# McPiFace-60mmFan-V3_1.net
KiCad netlist of a schematic drawn in EAGLE
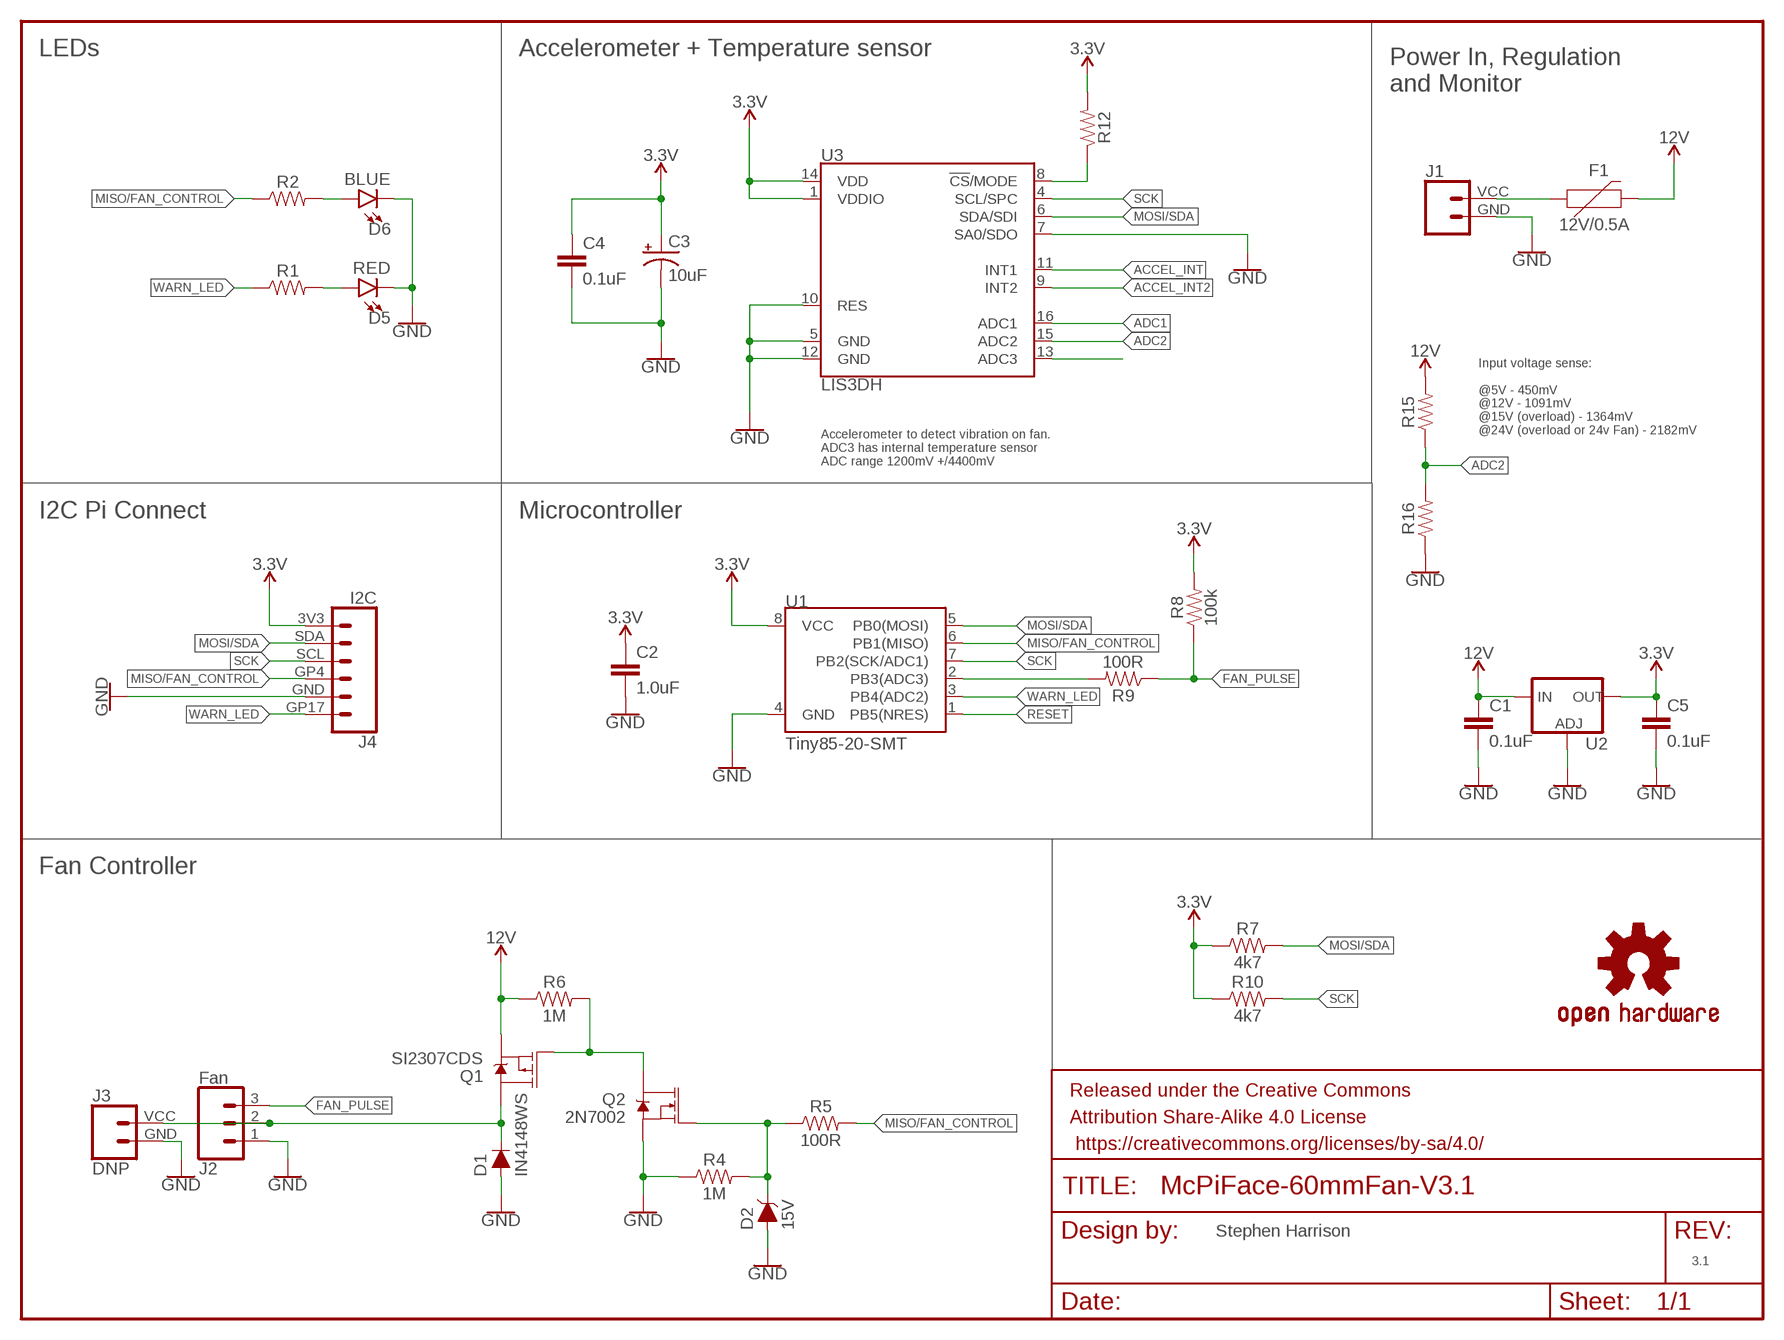
[diagram p0: schematic, sheet 1]

(export (version "E")
  (design (tool "Eeschema 10.0.6"))
  (components
    (comp (ref "C1")
      (value "0.1uF")
      (footprint "eagle-import:0805")
      (libsource (lib "eagle-import") (part "0.1UF-0805-25V"))
    )
    (comp (ref "C2")
      (value "1.0uF")
      (footprint "eagle-import:0805")
      (libsource (lib "eagle-import") (part "1.0UF-0805-25V-10%"))
    )
    (comp (ref "C3")
      (value "10uF")
      (footprint "eagle-import:EIA3216")
      (libsource (lib "eagle-import") (part "10UF-16V-10%(TANT)"))
    )
    (comp (ref "C4")
      (value "0.1uF")
      (footprint "eagle-import:0805")
      (libsource (lib "eagle-import") (part "1.0UF-0805-25V-10%"))
    )
    (comp (ref "C5")
      (value "0.1uF")
      (footprint "eagle-import:0805")
      (libsource (lib "eagle-import") (part "0.1UF-0805-25V"))
    )
    (comp (ref "D1")
      (value "IN4148WS")
      (footprint "eagle-import:SOD-323")
      (libsource (lib "eagle-import") (part "DIODE-BAS16J"))
    )
    (comp (ref "D2")
      (value "15V")
      (footprint "eagle-import:SOD-323")
      (libsource (lib "eagle-import") (part "DIODE-ZENER-BZT52C3V6S"))
    )
    (comp (ref "D5")
      (value "RED")
      (footprint "eagle-import:LED-1206")
      (libsource (lib "eagle-import") (part "LED1206"))
    )
    (comp (ref "D6")
      (value "BLUE")
      (footprint "eagle-import:LED-1206")
      (libsource (lib "eagle-import") (part "LED1206"))
    )
    (comp (ref "F1")
      (value "12V/0.5A")
      (footprint "eagle-import:1206")
      (libsource (lib "eagle-import") (part "PPTC_HALF-AMP"))
    )
    (comp (ref "FRAME1")
      (value "FRAME-LETTER")
      (footprint "eagle-import:CREATIVE_COMMONS")
      (libsource (lib "eagle-import") (part "FRAME-LETTER"))
    )
    (comp (ref "J1")
      (value "CONN_024UCON-15767")
      (footprint "eagle-import:JST-2-SMD-VERT")
      (libsource (lib "eagle-import") (part "CONN_024UCON-15767"))
    )
    (comp (ref "J2")
      (value "Fan")
      (footprint "eagle-import:JST-3-SMD")
      (fields (field (name "MFG") "S3B-PH-SM4-TB(LF)(SN)"))
      (libsource (lib "eagle-import") (part "CONN_03JST-SMD"))
    )
    (comp (ref "J3")
      (value "DNP")
      (footprint "eagle-import:JST-2-SMD-VERT")
      (libsource (lib "eagle-import") (part "CONN_024UCON-15767"))
    )
    (comp (ref "J4")
      (value "I2C")
      (footprint "eagle-import:JST-6-SH-1.0MM-TOP")
      (libsource (lib "eagle-import") (part "MC_PI_FACE_I2CTOP"))
    )
    (comp (ref "LOGO1")
      (value "OSHW-LOGOL")
      (footprint "eagle-import:OSHW-LOGO-L")
      (libsource (lib "eagle-import") (part "OSHW-LOGOL"))
    )
    (comp (ref "Q1")
      (value "SI2307CDS")
      (footprint "eagle-import:SOT23-3")
      (libsource (lib "eagle-import") (part "MOSFET_PCH-IRLML2244"))
    )
    (comp (ref "Q2")
      (value "2N7002")
      (footprint "eagle-import:SOT23-3")
      (libsource (lib "eagle-import") (part "MOSFET-NCH-BSS138"))
    )
    (comp (ref "R1")
      (value "RESISTOR0805")
      (footprint "eagle-import:0805")
      (libsource (lib "eagle-import") (part "RESISTOR0805"))
    )
    (comp (ref "R2")
      (value "RESISTOR0805")
      (footprint "eagle-import:0805")
      (libsource (lib "eagle-import") (part "RESISTOR0805"))
    )
    (comp (ref "R4")
      (value "1M")
      (footprint "eagle-import:0805")
      (libsource (lib "eagle-import") (part "RESISTOR0805"))
    )
    (comp (ref "R5")
      (value "100R")
      (footprint "eagle-import:0805")
      (libsource (lib "eagle-import") (part "RESISTOR0805"))
    )
    (comp (ref "R6")
      (value "1M")
      (footprint "eagle-import:0805")
      (libsource (lib "eagle-import") (part "RESISTOR0805"))
    )
    (comp (ref "R7")
      (value "4k7")
      (footprint "eagle-import:0805")
      (libsource (lib "eagle-import") (part "RESISTOR0805"))
    )
    (comp (ref "R8")
      (value "100k")
      (footprint "eagle-import:0805")
      (libsource (lib "eagle-import") (part "RESISTOR0805"))
    )
    (comp (ref "R9")
      (value "100R")
      (footprint "eagle-import:0805")
      (libsource (lib "eagle-import") (part "RESISTOR0805"))
    )
    (comp (ref "R10")
      (value "4k7")
      (footprint "eagle-import:0805")
      (libsource (lib "eagle-import") (part "RESISTOR0805"))
    )
    (comp (ref "R12")
      (value "RESISTOR0805")
      (footprint "eagle-import:0805")
      (libsource (lib "eagle-import") (part "RESISTOR0805"))
    )
    (comp (ref "R15")
      (value "RESISTOR0805")
      (footprint "eagle-import:0805")
      (libsource (lib "eagle-import") (part "RESISTOR0805"))
    )
    (comp (ref "R16")
      (value "RESISTOR0805")
      (footprint "eagle-import:0805")
      (libsource (lib "eagle-import") (part "RESISTOR0805"))
    )
    (comp (ref "U1")
      (value "Tiny85-20-SMT")
      (footprint "eagle-import:SO08-EIAJ")
      (libsource (lib "eagle-import") (part "ATTINY45TINY85-20-SMT"))
    )
    (comp (ref "U2")
      (value "V_REG_LM1117SOT223")
      (footprint "eagle-import:SOT223")
      (libsource (lib "eagle-import") (part "V_REG_LM1117SOT223"))
    )
    (comp (ref "U3")
      (value "LIS3DH")
      (footprint "eagle-import:LGA-16-3X3")
      (libsource (lib "eagle-import") (part "LIS3DH"))
    )
  )
  (nets
    (net (code "1") (name "3.3V") (class "Default")
      (node (ref "C2") (pin "1") (pinfunction "1_1") (pintype "passive"))
      (node (ref "C3") (pin "A") (pinfunction "+_A") (pintype "passive"))
      (node (ref "C4") (pin "1") (pinfunction "1_1") (pintype "passive"))
      (node (ref "C5") (pin "1") (pinfunction "1_1") (pintype "passive"))
      (node (ref "J4") (pin "3V3") (pinfunction "3V3_3V3") (pintype "power_in"))
      (node (ref "R10") (pin "1") (pinfunction "1_1") (pintype "passive"))
      (node (ref "R12") (pin "2") (pinfunction "2_2") (pintype "passive"))
      (node (ref "R7") (pin "1") (pinfunction "1_1") (pintype "passive"))
      (node (ref "R8") (pin "2") (pinfunction "2_2") (pintype "passive"))
      (node (ref "U1") (pin "8") (pinfunction "VCC_8") (pintype "bidirectional"))
      (node (ref "U2") (pin "2") (pinfunction "OUT_2") (pintype "output"))
      (node (ref "U2") (pin "4") (pinfunction "OUT_4") (pintype "output"))
      (node (ref "U3") (pin "1") (pinfunction "VDDIO_1") (pintype "bidirectional"))
      (node (ref "U3") (pin "14") (pinfunction "VDD_14") (pintype "bidirectional"))
    )
    (net (code "2") (name "12V") (class "Default")
      (node (ref "C1") (pin "1") (pinfunction "1_1") (pintype "passive"))
      (node (ref "F1") (pin "2") (pinfunction "2_2") (pintype "bidirectional"))
      (node (ref "Q1") (pin "2") (pinfunction "S_2") (pintype "bidirectional"))
      (node (ref "R15") (pin "2") (pinfunction "2_2") (pintype "passive"))
      (node (ref "R6") (pin "1") (pinfunction "1_1") (pintype "passive"))
      (node (ref "U2") (pin "3") (pinfunction "IN_3") (pintype "input"))
    )
    (net (code "3") (name "ACCEL_INT") (class "Default")
      (node (ref "U3") (pin "11") (pinfunction "INT1_11") (pintype "bidirectional"))
    )
    (net (code "4") (name "ACCEL_INT2") (class "Default")
      (node (ref "U3") (pin "9") (pinfunction "INT2_9") (pintype "bidirectional"))
    )
    (net (code "5") (name "ADC1") (class "Default")
      (node (ref "U3") (pin "16") (pinfunction "ADC1_16") (pintype "bidirectional"))
    )
    (net (code "6") (name "ADC2") (class "Default")
      (node (ref "R15") (pin "1") (pinfunction "1_1") (pintype "passive"))
      (node (ref "R16") (pin "2") (pinfunction "2_2") (pintype "passive"))
      (node (ref "U3") (pin "15") (pinfunction "ADC2_15") (pintype "bidirectional"))
    )
    (net (code "7") (name "FAN_PULSE") (class "Default")
      (node (ref "J2") (pin "3") (pinfunction "1_3") (pintype "passive"))
      (node (ref "R8") (pin "1") (pinfunction "1_1") (pintype "passive"))
      (node (ref "R9") (pin "1") (pinfunction "1_1") (pintype "passive"))
    )
    (net (code "8") (name "GND") (class "Default")
      (node (ref "C1") (pin "2") (pinfunction "2_2") (pintype "passive"))
      (node (ref "C2") (pin "2") (pinfunction "2_2") (pintype "passive"))
      (node (ref "C3") (pin "C") (pinfunction "-_C") (pintype "passive"))
      (node (ref "C4") (pin "2") (pinfunction "2_2") (pintype "passive"))
      (node (ref "C5") (pin "2") (pinfunction "2_2") (pintype "passive"))
      (node (ref "D1") (pin "A") (pinfunction "A_A") (pintype "passive"))
      (node (ref "D2") (pin "A") (pinfunction "A_A") (pintype "passive"))
      (node (ref "D5") (pin "C") (pinfunction "C_C") (pintype "passive"))
      (node (ref "D6") (pin "C") (pinfunction "C_C") (pintype "passive"))
      (node (ref "J1") (pin "GND") (pinfunction "1_GND") (pintype "passive"))
      (node (ref "J2") (pin "1") (pinfunction "3_1") (pintype "passive"))
      (node (ref "J3") (pin "GND") (pinfunction "1_GND") (pintype "passive"))
      (node (ref "J4") (pin "GND") (pinfunction "GND_GND") (pintype "power_in"))
      (node (ref "Q2") (pin "2") (pinfunction "S_2") (pintype "bidirectional"))
      (node (ref "R16") (pin "1") (pinfunction "1_1") (pintype "passive"))
      (node (ref "R4") (pin "1") (pinfunction "1_1") (pintype "passive"))
      (node (ref "U1") (pin "4") (pinfunction "GND_4") (pintype "bidirectional"))
      (node (ref "U2") (pin "1") (pinfunction "ADJ_1") (pintype "input"))
      (node (ref "U3") (pin "10") (pinfunction "RES_10") (pintype "bidirectional"))
      (node (ref "U3") (pin "12") (pinfunction "GND_12") (pintype "bidirectional"))
      (node (ref "U3") (pin "5") (pinfunction "GND_5") (pintype "bidirectional"))
      (node (ref "U3") (pin "7") (pinfunction "SA0/SDO_7") (pintype "bidirectional"))
    )
    (net (code "9") (name "MISO{slash}FAN_CONTROL") (class "Default")
      (node (ref "J4") (pin "GP4") (pinfunction "GP4_GP4") (pintype "bidirectional"))
      (node (ref "R2") (pin "1") (pinfunction "1_1") (pintype "passive"))
      (node (ref "R5") (pin "2") (pinfunction "2_2") (pintype "passive"))
      (node (ref "U1") (pin "6") (pinfunction "PB1(MISO)_6") (pintype "bidirectional"))
    )
    (net (code "10") (name "MOSI{slash}SDA") (class "Default")
      (node (ref "J4") (pin "SDA") (pinfunction "SDA_SDA") (pintype "bidirectional"))
      (node (ref "R7") (pin "2") (pinfunction "2_2") (pintype "passive"))
      (node (ref "U1") (pin "5") (pinfunction "PB0(MOSI)_5") (pintype "bidirectional"))
      (node (ref "U3") (pin "6") (pinfunction "SDA/SDI_6") (pintype "bidirectional"))
    )
    (net (code "11") (name "Net-(D5-PadA)") (class "Default")
      (node (ref "D5") (pin "A") (pinfunction "A_A") (pintype "passive"))
      (node (ref "R1") (pin "2") (pinfunction "2_2") (pintype "passive"))
    )
    (net (code "12") (name "Net-(D6-PadA)") (class "Default")
      (node (ref "D6") (pin "A") (pinfunction "A_A") (pintype "passive"))
      (node (ref "R2") (pin "2") (pinfunction "2_2") (pintype "passive"))
    )
    (net (code "13") (name "Net-(J1-2)") (class "Default")
      (node (ref "F1") (pin "1") (pinfunction "1_1") (pintype "bidirectional"))
      (node (ref "J1") (pin "VCC") (pinfunction "2_VCC") (pintype "passive"))
    )
    (net (code "14") (name "Net-(J3-2)") (class "Default")
      (node (ref "D1") (pin "C") (pinfunction "C_C") (pintype "passive"))
      (node (ref "J2") (pin "2") (pinfunction "2_2") (pintype "passive"))
      (node (ref "J3") (pin "VCC") (pinfunction "2_VCC") (pintype "passive"))
      (node (ref "Q1") (pin "3") (pinfunction "D_3") (pintype "bidirectional"))
    )
    (net (code "15") (name "Net-(Q1-G)") (class "Default")
      (node (ref "Q1") (pin "1") (pinfunction "G_1") (pintype "bidirectional"))
      (node (ref "Q2") (pin "3") (pinfunction "D_3") (pintype "bidirectional"))
      (node (ref "R6") (pin "2") (pinfunction "2_2") (pintype "passive"))
    )
    (net (code "16") (name "Net-(Q2-G)") (class "Default")
      (node (ref "D2") (pin "C") (pinfunction "C_C") (pintype "passive"))
      (node (ref "Q2") (pin "1") (pinfunction "G_1") (pintype "bidirectional"))
      (node (ref "R4") (pin "2") (pinfunction "2_2") (pintype "passive"))
      (node (ref "R5") (pin "1") (pinfunction "1_1") (pintype "passive"))
    )
    (net (code "17") (name "Net-(U1-PB3(ADC3))") (class "Default")
      (node (ref "R9") (pin "2") (pinfunction "2_2") (pintype "passive"))
      (node (ref "U1") (pin "2") (pinfunction "PB3(ADC3)_2") (pintype "bidirectional"))
    )
    (net (code "18") (name "Net-(U3-~{CS}{slash}MODE)") (class "Default")
      (node (ref "R12") (pin "1") (pinfunction "1_1") (pintype "passive"))
      (node (ref "U3") (pin "8") (pinfunction "~{CS}/MODE_8") (pintype "bidirectional"))
    )
    (net (code "19") (name "RESET") (class "Default")
      (node (ref "U1") (pin "1") (pinfunction "PB5(NRES)_1") (pintype "bidirectional"))
    )
    (net (code "20") (name "SCK") (class "Default")
      (node (ref "J4") (pin "SCL") (pinfunction "SCL_SCL") (pintype "bidirectional"))
      (node (ref "R10") (pin "2") (pinfunction "2_2") (pintype "passive"))
      (node (ref "U1") (pin "7") (pinfunction "PB2(SCK/ADC1)_7") (pintype "bidirectional"))
      (node (ref "U3") (pin "4") (pinfunction "SCL/SPC_4") (pintype "bidirectional"))
    )
    (net (code "21") (name "WARN_LED") (class "Default")
      (node (ref "J4") (pin "GP17") (pinfunction "GP17_GP17") (pintype "bidirectional"))
      (node (ref "R1") (pin "1") (pinfunction "1_1") (pintype "passive"))
      (node (ref "U1") (pin "3") (pinfunction "PB4(ADC2)_3") (pintype "bidirectional"))
    )
    (net (code "22") (name "unconnected-(U3-ADC3-Pad13)") (class "Default")
      (node (ref "U3") (pin "13") (pinfunction "ADC3_13") (pintype "bidirectional"))
    )
  )
)
